# Electrical_Schematic.net
KiCad netlist of a schematic drawn in Altium Designer
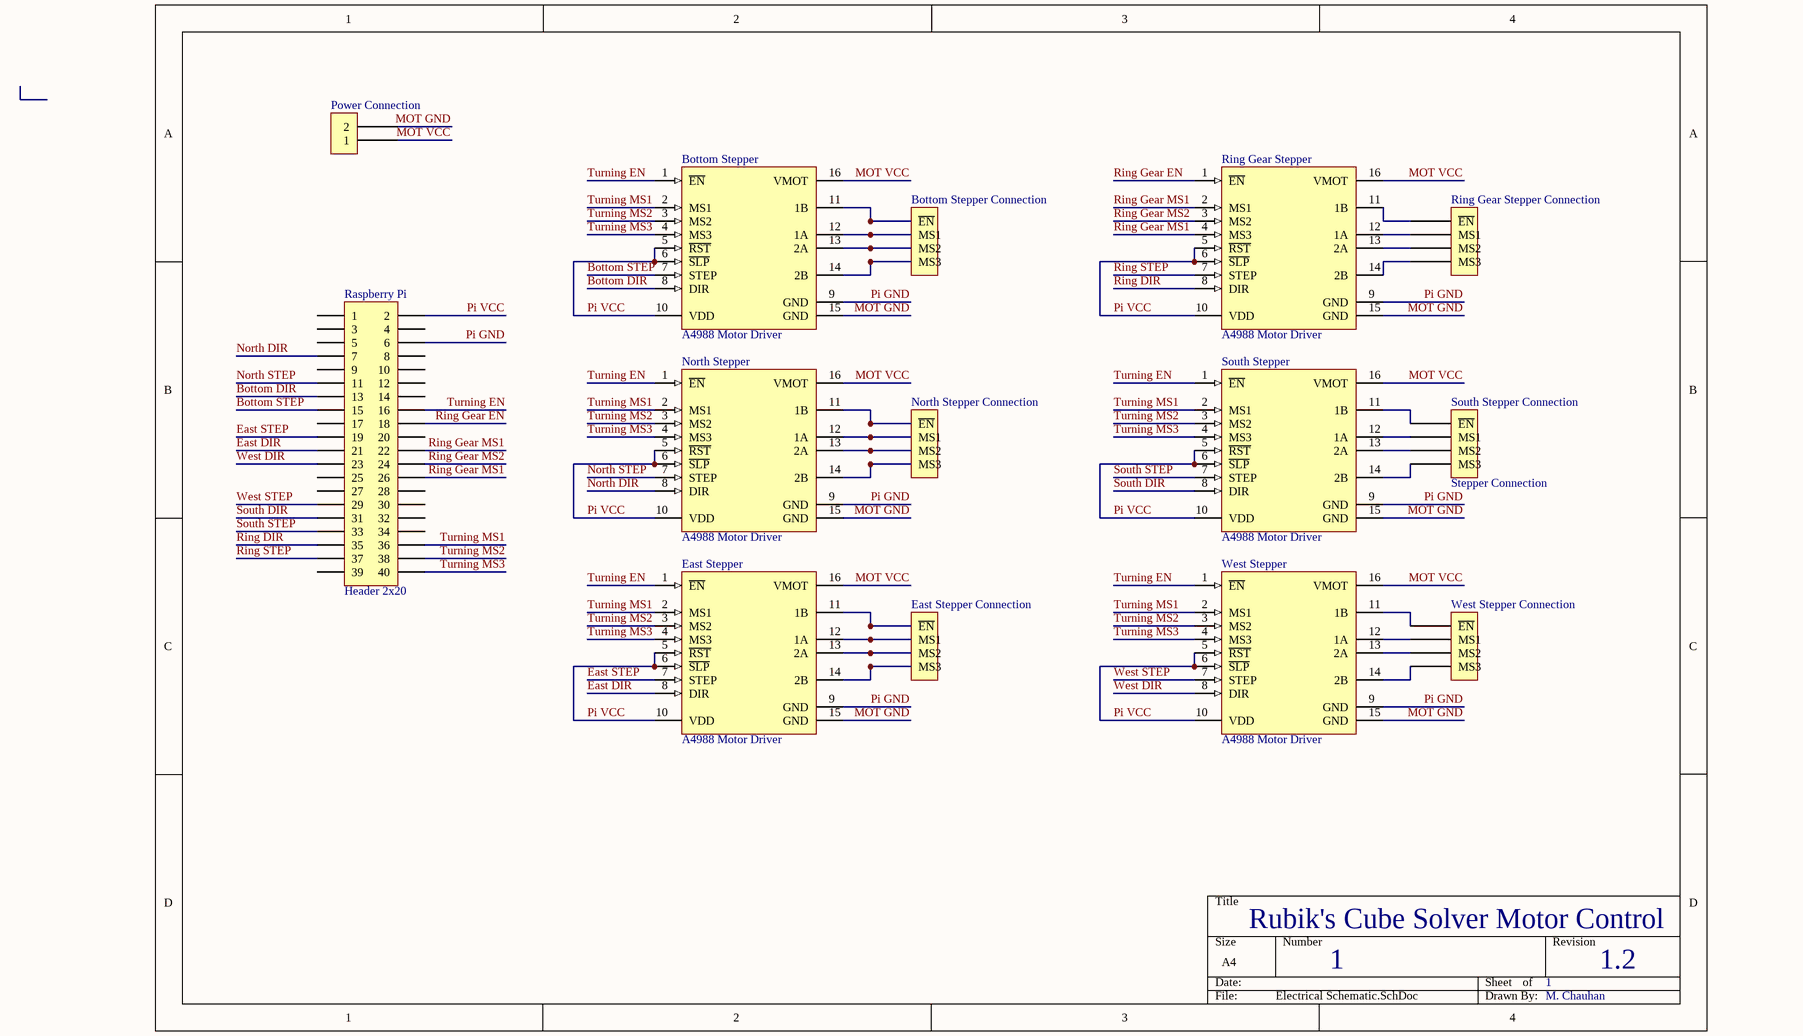
[diagram p0: Electrical Schematic.SchDoc]

(export (version "E")
  (design (tool "Eeschema 10.0.6"))
  (components
    (comp (ref "Bottom Stepper")
      (value "A4988 Motor Driver")
      (footprint "Polo-A4988 Motor Driver_V")
      (description "Stepper Motor Driver Carrier, 3 to 5.5 V, 2 A, 16-Pin THD")
      (fields (field (name "MANUFACTURER") "Pololu Robotics & Electronics"))
      (libsource (lib "Mantaj Chauhan") (part "POLO-A4988-16"))
    )
    (comp (ref "Bottom Stepper Connection")
      (value "~")
      (footprint "Header 1x4 male")
      (libsource (lib "Headers") (part "Header 4x1"))
    )
    (comp (ref "East Stepper")
      (value "A4988 Motor Driver")
      (footprint "Polo-A4988 Motor Driver_V")
      (description "Stepper Motor Driver Carrier, 3 to 5.5 V, 2 A, 16-Pin THD")
      (fields (field (name "MANUFACTURER") "Pololu Robotics & Electronics"))
      (libsource (lib "Mantaj Chauhan") (part "POLO-A4988-16"))
    )
    (comp (ref "East Stepper Connection")
      (value "~")
      (footprint "Header 1x4 male")
      (libsource (lib "Headers") (part "Header 4x1"))
    )
    (comp (ref "North Stepper")
      (value "A4988 Motor Driver")
      (footprint "Polo-A4988 Motor Driver_V")
      (description "Stepper Motor Driver Carrier, 3 to 5.5 V, 2 A, 16-Pin THD")
      (fields (field (name "MANUFACTURER") "Pololu Robotics & Electronics"))
      (libsource (lib "Mantaj Chauhan") (part "POLO-A4988-16"))
    )
    (comp (ref "North Stepper Connection")
      (value "~")
      (footprint "Header 1x4 male")
      (libsource (lib "Headers") (part "Header 4x1"))
    )
    (comp (ref "Power Connection")
      (value "~")
      (footprint "Header 1x2+1 1.0mm")
      (libsource (lib "Headers") (part "Header 2x1"))
    )
    (comp (ref "Raspberry Pi")
      (value "Header 2x20")
      (footprint "Header 2x20 MALE")
      (libsource (lib "Headers") (part "Header 2x20"))
    )
    (comp (ref "Ring Gear Stepper")
      (value "A4988 Motor Driver")
      (footprint "Polo-A4988 Motor Driver_V")
      (description "Stepper Motor Driver Carrier, 3 to 5.5 V, 2 A, 16-Pin THD")
      (fields (field (name "MANUFACTURER") "Pololu Robotics & Electronics"))
      (libsource (lib "Mantaj Chauhan") (part "POLO-A4988-16"))
    )
    (comp (ref "Ring Gear Stepper Connection")
      (value "~")
      (footprint "Header 1x4 male")
      (libsource (lib "Headers") (part "Header 4x1"))
    )
    (comp (ref "South Stepper")
      (value "A4988 Motor Driver")
      (footprint "Polo-A4988 Motor Driver_V")
      (description "Stepper Motor Driver Carrier, 3 to 5.5 V, 2 A, 16-Pin THD")
      (fields (field (name "MANUFACTURER") "Pololu Robotics & Electronics"))
      (libsource (lib "Mantaj Chauhan") (part "POLO-A4988-16"))
    )
    (comp (ref "South Stepper Connection")
      (value "Stepper Connection")
      (footprint "Header 1x4 male")
      (libsource (lib "Headers") (part "Header 4x1"))
    )
    (comp (ref "West Stepper")
      (value "A4988 Motor Driver")
      (footprint "Polo-A4988 Motor Driver_V")
      (description "Stepper Motor Driver Carrier, 3 to 5.5 V, 2 A, 16-Pin THD")
      (fields (field (name "MANUFACTURER") "Pololu Robotics & Electronics"))
      (libsource (lib "Mantaj Chauhan") (part "POLO-A4988-16"))
    )
    (comp (ref "West Stepper Connection")
      (value "~")
      (footprint "Header 1x4 male")
      (libsource (lib "Headers") (part "Header 4x1"))
    )
  )
  (nets
    (net (code "1") (name "/Bottom DIR") (class "Default")
      (node (ref "Bottom Stepper") (pin "8") (pinfunction "DIR_8") (pintype "input"))
      (node (ref "Raspberry Pi") (pin "13") (pinfunction "13_13") (pintype "passive"))
    )
    (net (code "2") (name "/Bottom STEP") (class "Default")
      (node (ref "Bottom Stepper") (pin "7") (pinfunction "STEP_7") (pintype "input"))
      (node (ref "Raspberry Pi") (pin "15") (pinfunction "15_15") (pintype "passive"))
    )
    (net (code "3") (name "/East DIR") (class "Default")
      (node (ref "East Stepper") (pin "8") (pinfunction "DIR_8") (pintype "input"))
      (node (ref "Raspberry Pi") (pin "21") (pinfunction "21_21") (pintype "passive"))
    )
    (net (code "4") (name "/East STEP") (class "Default")
      (node (ref "East Stepper") (pin "7") (pinfunction "STEP_7") (pintype "input"))
      (node (ref "Raspberry Pi") (pin "19") (pinfunction "19_19") (pintype "passive"))
    )
    (net (code "5") (name "/MOT GND") (class "Default")
      (node (ref "Bottom Stepper") (pin "15") (pinfunction "GND_15") (pintype "power_in"))
      (node (ref "East Stepper") (pin "15") (pinfunction "GND_15") (pintype "power_in"))
      (node (ref "North Stepper") (pin "15") (pinfunction "GND_15") (pintype "power_in"))
      (node (ref "Power Connection") (pin "2") (pinfunction "2_2") (pintype "passive"))
      (node (ref "Ring Gear Stepper") (pin "15") (pinfunction "GND_15") (pintype "power_in"))
      (node (ref "South Stepper") (pin "15") (pinfunction "GND_15") (pintype "power_in"))
      (node (ref "West Stepper") (pin "15") (pinfunction "GND_15") (pintype "power_in"))
    )
    (net (code "6") (name "/MOT VCC") (class "Default")
      (node (ref "Bottom Stepper") (pin "16") (pinfunction "VMOT_16") (pintype "power_in"))
      (node (ref "East Stepper") (pin "16") (pinfunction "VMOT_16") (pintype "power_in"))
      (node (ref "North Stepper") (pin "16") (pinfunction "VMOT_16") (pintype "power_in"))
      (node (ref "Power Connection") (pin "1") (pinfunction "1_1") (pintype "passive"))
      (node (ref "Ring Gear Stepper") (pin "16") (pinfunction "VMOT_16") (pintype "power_in"))
      (node (ref "South Stepper") (pin "16") (pinfunction "VMOT_16") (pintype "power_in"))
      (node (ref "West Stepper") (pin "16") (pinfunction "VMOT_16") (pintype "power_in"))
    )
    (net (code "7") (name "/North DIR") (class "Default")
      (node (ref "North Stepper") (pin "8") (pinfunction "DIR_8") (pintype "input"))
      (node (ref "Raspberry Pi") (pin "7") (pinfunction "7_7") (pintype "passive"))
    )
    (net (code "8") (name "/North STEP") (class "Default")
      (node (ref "North Stepper") (pin "7") (pinfunction "STEP_7") (pintype "input"))
      (node (ref "Raspberry Pi") (pin "11") (pinfunction "11_11") (pintype "passive"))
    )
    (net (code "9") (name "/Pi GND") (class "Default")
      (node (ref "Bottom Stepper") (pin "9") (pinfunction "GND_9") (pintype "power_in"))
      (node (ref "East Stepper") (pin "9") (pinfunction "GND_9") (pintype "power_in"))
      (node (ref "North Stepper") (pin "9") (pinfunction "GND_9") (pintype "power_in"))
      (node (ref "Raspberry Pi") (pin "6") (pinfunction "6_6") (pintype "passive"))
      (node (ref "Ring Gear Stepper") (pin "9") (pinfunction "GND_9") (pintype "power_in"))
      (node (ref "South Stepper") (pin "9") (pinfunction "GND_9") (pintype "power_in"))
      (node (ref "West Stepper") (pin "9") (pinfunction "GND_9") (pintype "power_in"))
    )
    (net (code "10") (name "/Pi VCC") (class "Default")
      (node (ref "Bottom Stepper") (pin "10") (pinfunction "VDD_10") (pintype "power_in"))
      (node (ref "Bottom Stepper") (pin "5") (pinfunction "~{RST}_5") (pintype "input"))
      (node (ref "Bottom Stepper") (pin "6") (pinfunction "~{SLP}_6") (pintype "input"))
      (node (ref "East Stepper") (pin "10") (pinfunction "VDD_10") (pintype "power_in"))
      (node (ref "East Stepper") (pin "5") (pinfunction "~{RST}_5") (pintype "input"))
      (node (ref "East Stepper") (pin "6") (pinfunction "~{SLP}_6") (pintype "input"))
      (node (ref "North Stepper") (pin "10") (pinfunction "VDD_10") (pintype "power_in"))
      (node (ref "North Stepper") (pin "5") (pinfunction "~{RST}_5") (pintype "input"))
      (node (ref "North Stepper") (pin "6") (pinfunction "~{SLP}_6") (pintype "input"))
      (node (ref "Raspberry Pi") (pin "2") (pinfunction "2_2") (pintype "passive"))
      (node (ref "Ring Gear Stepper") (pin "10") (pinfunction "VDD_10") (pintype "power_in"))
      (node (ref "Ring Gear Stepper") (pin "5") (pinfunction "~{RST}_5") (pintype "input"))
      (node (ref "Ring Gear Stepper") (pin "6") (pinfunction "~{SLP}_6") (pintype "input"))
      (node (ref "South Stepper") (pin "10") (pinfunction "VDD_10") (pintype "power_in"))
      (node (ref "South Stepper") (pin "5") (pinfunction "~{RST}_5") (pintype "input"))
      (node (ref "South Stepper") (pin "6") (pinfunction "~{SLP}_6") (pintype "input"))
      (node (ref "West Stepper") (pin "10") (pinfunction "VDD_10") (pintype "power_in"))
      (node (ref "West Stepper") (pin "5") (pinfunction "~{RST}_5") (pintype "input"))
      (node (ref "West Stepper") (pin "6") (pinfunction "~{SLP}_6") (pintype "input"))
    )
    (net (code "11") (name "/Ring DIR") (class "Default")
      (node (ref "Raspberry Pi") (pin "35") (pinfunction "35_35") (pintype "passive"))
      (node (ref "Ring Gear Stepper") (pin "8") (pinfunction "DIR_8") (pintype "input"))
    )
    (net (code "12") (name "/Ring Gear EN") (class "Default")
      (node (ref "Raspberry Pi") (pin "18") (pinfunction "18_18") (pintype "passive"))
      (node (ref "Ring Gear Stepper") (pin "1") (pinfunction "~{EN}_1") (pintype "input"))
    )
    (net (code "13") (name "/Ring Gear MS1") (class "Default")
      (node (ref "Raspberry Pi") (pin "22") (pinfunction "22_22") (pintype "passive"))
      (node (ref "Raspberry Pi") (pin "26") (pinfunction "26_26") (pintype "passive"))
      (node (ref "Ring Gear Stepper") (pin "2") (pinfunction "MS1_2") (pintype "input"))
      (node (ref "Ring Gear Stepper") (pin "4") (pinfunction "MS3_4") (pintype "input"))
    )
    (net (code "14") (name "/Ring Gear MS2") (class "Default")
      (node (ref "Raspberry Pi") (pin "24") (pinfunction "24_24") (pintype "passive"))
      (node (ref "Ring Gear Stepper") (pin "3") (pinfunction "MS2_3") (pintype "input"))
    )
    (net (code "15") (name "/Ring STEP") (class "Default")
      (node (ref "Raspberry Pi") (pin "37") (pinfunction "37_37") (pintype "passive"))
      (node (ref "Ring Gear Stepper") (pin "7") (pinfunction "STEP_7") (pintype "input"))
    )
    (net (code "16") (name "/South DIR") (class "Default")
      (node (ref "Raspberry Pi") (pin "31") (pinfunction "31_31") (pintype "passive"))
      (node (ref "South Stepper") (pin "8") (pinfunction "DIR_8") (pintype "input"))
    )
    (net (code "17") (name "/South STEP") (class "Default")
      (node (ref "Raspberry Pi") (pin "33") (pinfunction "33_33") (pintype "passive"))
      (node (ref "South Stepper") (pin "7") (pinfunction "STEP_7") (pintype "input"))
    )
    (net (code "18") (name "/Turning EN") (class "Default")
      (node (ref "Bottom Stepper") (pin "1") (pinfunction "~{EN}_1") (pintype "input"))
      (node (ref "East Stepper") (pin "1") (pinfunction "~{EN}_1") (pintype "input"))
      (node (ref "North Stepper") (pin "1") (pinfunction "~{EN}_1") (pintype "input"))
      (node (ref "Raspberry Pi") (pin "16") (pinfunction "16_16") (pintype "passive"))
      (node (ref "South Stepper") (pin "1") (pinfunction "~{EN}_1") (pintype "input"))
      (node (ref "West Stepper") (pin "1") (pinfunction "~{EN}_1") (pintype "input"))
    )
    (net (code "19") (name "/Turning MS1") (class "Default")
      (node (ref "Bottom Stepper") (pin "2") (pinfunction "MS1_2") (pintype "input"))
      (node (ref "East Stepper") (pin "2") (pinfunction "MS1_2") (pintype "input"))
      (node (ref "North Stepper") (pin "2") (pinfunction "MS1_2") (pintype "input"))
      (node (ref "Raspberry Pi") (pin "36") (pinfunction "36_36") (pintype "passive"))
      (node (ref "South Stepper") (pin "2") (pinfunction "MS1_2") (pintype "input"))
      (node (ref "West Stepper") (pin "2") (pinfunction "MS1_2") (pintype "input"))
    )
    (net (code "20") (name "/Turning MS2") (class "Default")
      (node (ref "Bottom Stepper") (pin "3") (pinfunction "MS2_3") (pintype "input"))
      (node (ref "East Stepper") (pin "3") (pinfunction "MS2_3") (pintype "input"))
      (node (ref "North Stepper") (pin "3") (pinfunction "MS2_3") (pintype "input"))
      (node (ref "Raspberry Pi") (pin "38") (pinfunction "38_38") (pintype "passive"))
      (node (ref "South Stepper") (pin "3") (pinfunction "MS2_3") (pintype "input"))
      (node (ref "West Stepper") (pin "3") (pinfunction "MS2_3") (pintype "input"))
    )
    (net (code "21") (name "/Turning MS3") (class "Default")
      (node (ref "Bottom Stepper") (pin "4") (pinfunction "MS3_4") (pintype "input"))
      (node (ref "East Stepper") (pin "4") (pinfunction "MS3_4") (pintype "input"))
      (node (ref "North Stepper") (pin "4") (pinfunction "MS3_4") (pintype "input"))
      (node (ref "Raspberry Pi") (pin "40") (pinfunction "40_40") (pintype "passive"))
      (node (ref "South Stepper") (pin "4") (pinfunction "MS3_4") (pintype "input"))
      (node (ref "West Stepper") (pin "4") (pinfunction "MS3_4") (pintype "input"))
    )
    (net (code "22") (name "/West DIR") (class "Default")
      (node (ref "Raspberry Pi") (pin "23") (pinfunction "23_23") (pintype "passive"))
      (node (ref "West Stepper") (pin "8") (pinfunction "DIR_8") (pintype "input"))
    )
    (net (code "23") (name "/West STEP") (class "Default")
      (node (ref "Raspberry Pi") (pin "29") (pinfunction "29_29") (pintype "passive"))
      (node (ref "West Stepper") (pin "7") (pinfunction "STEP_7") (pintype "input"))
    )
    (net (code "24") (name "Net-(Bottom Stepper Connection-MS1)") (class "Default")
      (node (ref "Bottom Stepper") (pin "12") (pinfunction "1A_12") (pintype "power_in"))
      (node (ref "Bottom Stepper Connection") (pin "2") (pinfunction "MS1_2") (pintype "passive"))
    )
    (net (code "25") (name "Net-(Bottom Stepper Connection-MS2)") (class "Default")
      (node (ref "Bottom Stepper") (pin "13") (pinfunction "2A_13") (pintype "power_in"))
      (node (ref "Bottom Stepper Connection") (pin "3") (pinfunction "MS2_3") (pintype "passive"))
    )
    (net (code "26") (name "Net-(Bottom Stepper Connection-MS3)") (class "Default")
      (node (ref "Bottom Stepper") (pin "14") (pinfunction "2B_14") (pintype "power_in"))
      (node (ref "Bottom Stepper Connection") (pin "4") (pinfunction "MS3_4") (pintype "passive"))
    )
    (net (code "27") (name "Net-(Bottom Stepper Connection-~{EN})") (class "Default")
      (node (ref "Bottom Stepper") (pin "11") (pinfunction "1B_11") (pintype "power_in"))
      (node (ref "Bottom Stepper Connection") (pin "1") (pinfunction "~{EN}_1") (pintype "passive"))
    )
    (net (code "28") (name "Net-(East Stepper Connection-MS1)") (class "Default")
      (node (ref "East Stepper") (pin "12") (pinfunction "1A_12") (pintype "power_in"))
      (node (ref "East Stepper Connection") (pin "2") (pinfunction "MS1_2") (pintype "passive"))
    )
    (net (code "29") (name "Net-(East Stepper Connection-MS2)") (class "Default")
      (node (ref "East Stepper") (pin "13") (pinfunction "2A_13") (pintype "power_in"))
      (node (ref "East Stepper Connection") (pin "3") (pinfunction "MS2_3") (pintype "passive"))
    )
    (net (code "30") (name "Net-(East Stepper Connection-MS3)") (class "Default")
      (node (ref "East Stepper") (pin "14") (pinfunction "2B_14") (pintype "power_in"))
      (node (ref "East Stepper Connection") (pin "4") (pinfunction "MS3_4") (pintype "passive"))
    )
    (net (code "31") (name "Net-(East Stepper Connection-~{EN})") (class "Default")
      (node (ref "East Stepper") (pin "11") (pinfunction "1B_11") (pintype "power_in"))
      (node (ref "East Stepper Connection") (pin "1") (pinfunction "~{EN}_1") (pintype "passive"))
    )
    (net (code "32") (name "Net-(North Stepper Connection-MS1)") (class "Default")
      (node (ref "North Stepper") (pin "12") (pinfunction "1A_12") (pintype "power_in"))
      (node (ref "North Stepper Connection") (pin "2") (pinfunction "MS1_2") (pintype "passive"))
    )
    (net (code "33") (name "Net-(North Stepper Connection-MS2)") (class "Default")
      (node (ref "North Stepper") (pin "13") (pinfunction "2A_13") (pintype "power_in"))
      (node (ref "North Stepper Connection") (pin "3") (pinfunction "MS2_3") (pintype "passive"))
    )
    (net (code "34") (name "Net-(North Stepper Connection-MS3)") (class "Default")
      (node (ref "North Stepper") (pin "14") (pinfunction "2B_14") (pintype "power_in"))
      (node (ref "North Stepper Connection") (pin "4") (pinfunction "MS3_4") (pintype "passive"))
    )
    (net (code "35") (name "Net-(North Stepper Connection-~{EN})") (class "Default")
      (node (ref "North Stepper") (pin "11") (pinfunction "1B_11") (pintype "power_in"))
      (node (ref "North Stepper Connection") (pin "1") (pinfunction "~{EN}_1") (pintype "passive"))
    )
    (net (code "36") (name "Net-(Ring Gear Stepper Connection-MS1)") (class "Default")
      (node (ref "Ring Gear Stepper") (pin "12") (pinfunction "1A_12") (pintype "power_in"))
      (node (ref "Ring Gear Stepper Connection") (pin "2") (pinfunction "MS1_2") (pintype "passive"))
    )
    (net (code "37") (name "Net-(Ring Gear Stepper Connection-MS2)") (class "Default")
      (node (ref "Ring Gear Stepper") (pin "13") (pinfunction "2A_13") (pintype "power_in"))
      (node (ref "Ring Gear Stepper Connection") (pin "3") (pinfunction "MS2_3") (pintype "passive"))
    )
    (net (code "38") (name "Net-(Ring Gear Stepper Connection-MS3)") (class "Default")
      (node (ref "Ring Gear Stepper") (pin "14") (pinfunction "2B_14") (pintype "power_in"))
      (node (ref "Ring Gear Stepper Connection") (pin "4") (pinfunction "MS3_4") (pintype "passive"))
    )
    (net (code "39") (name "Net-(Ring Gear Stepper Connection-~{EN})") (class "Default")
      (node (ref "Ring Gear Stepper") (pin "11") (pinfunction "1B_11") (pintype "power_in"))
      (node (ref "Ring Gear Stepper Connection") (pin "1") (pinfunction "~{EN}_1") (pintype "passive"))
    )
    (net (code "40") (name "Net-(South Stepper Connection-MS1)") (class "Default")
      (node (ref "South Stepper") (pin "12") (pinfunction "1A_12") (pintype "power_in"))
      (node (ref "South Stepper Connection") (pin "2") (pinfunction "MS1_2") (pintype "passive"))
    )
    (net (code "41") (name "Net-(South Stepper Connection-MS2)") (class "Default")
      (node (ref "South Stepper") (pin "13") (pinfunction "2A_13") (pintype "power_in"))
      (node (ref "South Stepper Connection") (pin "3") (pinfunction "MS2_3") (pintype "passive"))
    )
    (net (code "42") (name "Net-(South Stepper Connection-MS3)") (class "Default")
      (node (ref "South Stepper") (pin "14") (pinfunction "2B_14") (pintype "power_in"))
      (node (ref "South Stepper Connection") (pin "4") (pinfunction "MS3_4") (pintype "passive"))
    )
    (net (code "43") (name "Net-(South Stepper Connection-~{EN})") (class "Default")
      (node (ref "South Stepper") (pin "11") (pinfunction "1B_11") (pintype "power_in"))
      (node (ref "South Stepper Connection") (pin "1") (pinfunction "~{EN}_1") (pintype "passive"))
    )
    (net (code "44") (name "Net-(West Stepper Connection-MS1)") (class "Default")
      (node (ref "West Stepper") (pin "12") (pinfunction "1A_12") (pintype "power_in"))
      (node (ref "West Stepper Connection") (pin "2") (pinfunction "MS1_2") (pintype "passive"))
    )
    (net (code "45") (name "Net-(West Stepper Connection-MS2)") (class "Default")
      (node (ref "West Stepper") (pin "13") (pinfunction "2A_13") (pintype "power_in"))
      (node (ref "West Stepper Connection") (pin "3") (pinfunction "MS2_3") (pintype "passive"))
    )
    (net (code "46") (name "Net-(West Stepper Connection-MS3)") (class "Default")
      (node (ref "West Stepper") (pin "14") (pinfunction "2B_14") (pintype "power_in"))
      (node (ref "West Stepper Connection") (pin "4") (pinfunction "MS3_4") (pintype "passive"))
    )
    (net (code "47") (name "Net-(West Stepper Connection-~{EN})") (class "Default")
      (node (ref "West Stepper") (pin "11") (pinfunction "1B_11") (pintype "power_in"))
      (node (ref "West Stepper Connection") (pin "1") (pinfunction "~{EN}_1") (pintype "passive"))
    )
    (net (code "48") (name "unconnected-(Raspberry Pi-Pad1)") (class "Default")
      (node (ref "Raspberry Pi") (pin "1") (pinfunction "1_1") (pintype "passive"))
    )
    (net (code "49") (name "unconnected-(Raspberry Pi-Pad3)") (class "Default")
      (node (ref "Raspberry Pi") (pin "3") (pinfunction "3_3") (pintype "passive"))
    )
    (net (code "50") (name "unconnected-(Raspberry Pi-Pad4)") (class "Default")
      (node (ref "Raspberry Pi") (pin "4") (pinfunction "4_4") (pintype "passive"))
    )
    (net (code "51") (name "unconnected-(Raspberry Pi-Pad5)") (class "Default")
      (node (ref "Raspberry Pi") (pin "5") (pinfunction "5_5") (pintype "passive"))
    )
    (net (code "52") (name "unconnected-(Raspberry Pi-Pad8)") (class "Default")
      (node (ref "Raspberry Pi") (pin "8") (pinfunction "8_8") (pintype "passive"))
    )
    (net (code "53") (name "unconnected-(Raspberry Pi-Pad9)") (class "Default")
      (node (ref "Raspberry Pi") (pin "9") (pinfunction "9_9") (pintype "passive"))
    )
    (net (code "54") (name "unconnected-(Raspberry Pi-Pad10)") (class "Default")
      (node (ref "Raspberry Pi") (pin "10") (pinfunction "10_10") (pintype "passive"))
    )
    (net (code "55") (name "unconnected-(Raspberry Pi-Pad12)") (class "Default")
      (node (ref "Raspberry Pi") (pin "12") (pinfunction "12_12") (pintype "passive"))
    )
    (net (code "56") (name "unconnected-(Raspberry Pi-Pad14)") (class "Default")
      (node (ref "Raspberry Pi") (pin "14") (pinfunction "14_14") (pintype "passive"))
    )
    (net (code "57") (name "unconnected-(Raspberry Pi-Pad17)") (class "Default")
      (node (ref "Raspberry Pi") (pin "17") (pinfunction "17_17") (pintype "passive"))
    )
    (net (code "58") (name "unconnected-(Raspberry Pi-Pad20)") (class "Default")
      (node (ref "Raspberry Pi") (pin "20") (pinfunction "20_20") (pintype "passive"))
    )
    (net (code "59") (name "unconnected-(Raspberry Pi-Pad25)") (class "Default")
      (node (ref "Raspberry Pi") (pin "25") (pinfunction "25_25") (pintype "passive"))
    )
    (net (code "60") (name "unconnected-(Raspberry Pi-Pad27)") (class "Default")
      (node (ref "Raspberry Pi") (pin "27") (pinfunction "27_27") (pintype "passive"))
    )
    (net (code "61") (name "unconnected-(Raspberry Pi-Pad28)") (class "Default")
      (node (ref "Raspberry Pi") (pin "28") (pinfunction "28_28") (pintype "passive"))
    )
    (net (code "62") (name "unconnected-(Raspberry Pi-Pad30)") (class "Default")
      (node (ref "Raspberry Pi") (pin "30") (pinfunction "30_30") (pintype "passive"))
    )
    (net (code "63") (name "unconnected-(Raspberry Pi-Pad32)") (class "Default")
      (node (ref "Raspberry Pi") (pin "32") (pinfunction "32_32") (pintype "passive"))
    )
    (net (code "64") (name "unconnected-(Raspberry Pi-Pad34)") (class "Default")
      (node (ref "Raspberry Pi") (pin "34") (pinfunction "34_34") (pintype "passive"))
    )
    (net (code "65") (name "unconnected-(Raspberry Pi-Pad39)") (class "Default")
      (node (ref "Raspberry Pi") (pin "39") (pinfunction "39_39") (pintype "passive"))
    )
  )
)
